# deepblue.net
KiCad netlist of a schematic drawn in EAGLE
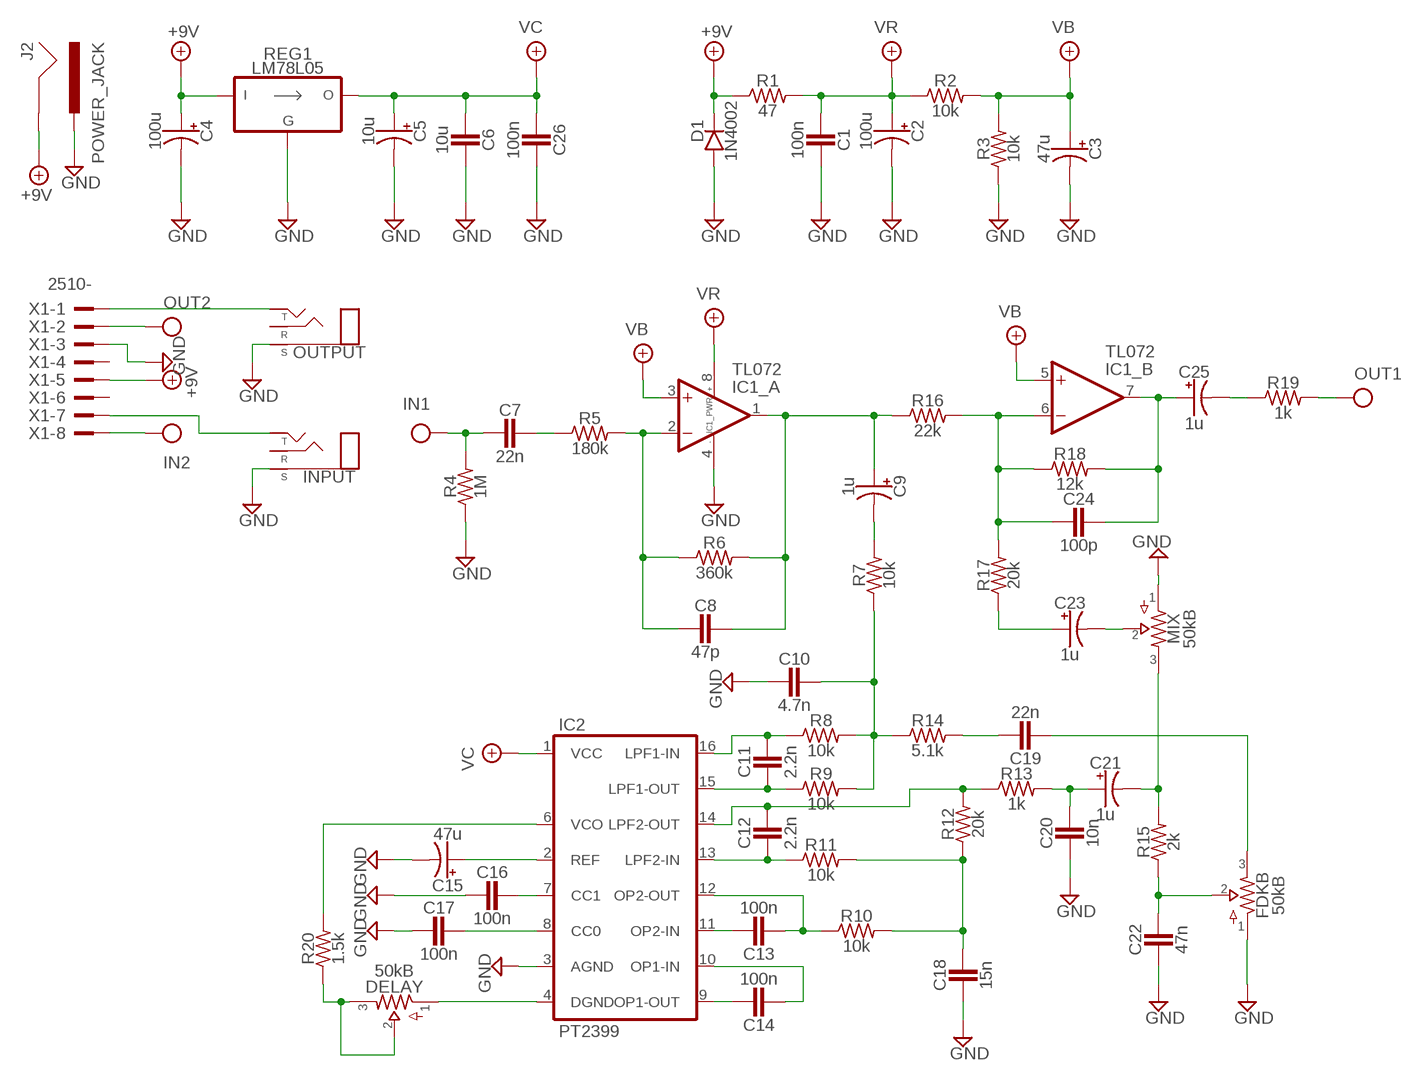
[diagram p0: schematic, sheet 1]

(export (version "E")
  (design (tool "Eeschema 10.0.6"))
  (components
    (comp (ref "C1")
      (value "100n")
      (footprint "eagle-import:050X030_025_2")
      (libsource (lib "eagle-import") (part "CER/FILM2"))
    )
    (comp (ref "C2")
      (value "100u")
      (footprint "eagle-import:050_020")
      (libsource (lib "eagle-import") (part "0500"))
    )
    (comp (ref "C3")
      (value "47u")
      (footprint "eagle-import:050_020")
      (libsource (lib "eagle-import") (part "0500"))
    )
    (comp (ref "C4")
      (value "100u")
      (footprint "eagle-import:050_020")
      (libsource (lib "eagle-import") (part "0500"))
    )
    (comp (ref "C5")
      (value "10u")
      (footprint "eagle-import:050_020")
      (libsource (lib "eagle-import") (part "0500"))
    )
    (comp (ref "C6")
      (value "10u")
      (footprint "eagle-import:050X030_025")
      (libsource (lib "eagle-import") (part "CER/FILM1"))
    )
    (comp (ref "C7")
      (value "22n")
      (footprint "eagle-import:BOX_SMALL")
      (libsource (lib "eagle-import") (part "CER/FILMBOX.1"))
    )
    (comp (ref "C8")
      (value "47p")
      (footprint "eagle-import:050X030_025_2")
      (libsource (lib "eagle-import") (part "CER/FILM2"))
    )
    (comp (ref "C9")
      (value "1u")
      (footprint "eagle-import:040_020")
      (libsource (lib "eagle-import") (part "0400"))
    )
    (comp (ref "C10")
      (value "4.7n")
      (footprint "eagle-import:BOX_SMALL")
      (libsource (lib "eagle-import") (part "CER/FILMBOX.1"))
    )
    (comp (ref "C11")
      (value "2.2n")
      (footprint "eagle-import:BOX_SMALL")
      (libsource (lib "eagle-import") (part "CER/FILMBOX.1"))
    )
    (comp (ref "C12")
      (value "2.2n")
      (footprint "eagle-import:BOX_SMALL")
      (libsource (lib "eagle-import") (part "CER/FILMBOX.1"))
    )
    (comp (ref "C13")
      (value "100n")
      (footprint "eagle-import:BOX_SMALL")
      (libsource (lib "eagle-import") (part "CER/FILMBOX.1"))
    )
    (comp (ref "C14")
      (value "100n")
      (footprint "eagle-import:BOX_SMALL")
      (libsource (lib "eagle-import") (part "CER/FILMBOX.1"))
    )
    (comp (ref "C15")
      (value "47u")
      (footprint "eagle-import:050_020")
      (libsource (lib "eagle-import") (part "0500"))
    )
    (comp (ref "C16")
      (value "100n")
      (footprint "eagle-import:BOX_SMALL")
      (libsource (lib "eagle-import") (part "CER/FILMBOX.1"))
    )
    (comp (ref "C17")
      (value "100n")
      (footprint "eagle-import:BOX_SMALL")
      (libsource (lib "eagle-import") (part "CER/FILMBOX.1"))
    )
    (comp (ref "C18")
      (value "15n")
      (footprint "eagle-import:BOX_SMALL")
      (libsource (lib "eagle-import") (part "CER/FILMBOX.1"))
    )
    (comp (ref "C19")
      (value "22n")
      (footprint "eagle-import:BOX_SMALL")
      (libsource (lib "eagle-import") (part "CER/FILMBOX.1"))
    )
    (comp (ref "C20")
      (value "10n")
      (footprint "eagle-import:BOX_SMALL")
      (libsource (lib "eagle-import") (part "CER/FILMBOX.1"))
    )
    (comp (ref "C21")
      (value "1u")
      (footprint "eagle-import:040_020")
      (libsource (lib "eagle-import") (part "0400"))
    )
    (comp (ref "C22")
      (value "47n")
      (footprint "eagle-import:BOX_SMALL")
      (libsource (lib "eagle-import") (part "CER/FILMBOX.1"))
    )
    (comp (ref "C23")
      (value "1u")
      (footprint "eagle-import:040_020")
      (libsource (lib "eagle-import") (part "0400"))
    )
    (comp (ref "C24")
      (value "100p")
      (footprint "eagle-import:050X030_025_2")
      (libsource (lib "eagle-import") (part "CER/FILM2"))
    )
    (comp (ref "C25")
      (value "1u")
      (footprint "eagle-import:040_020")
      (libsource (lib "eagle-import") (part "0400"))
    )
    (comp (ref "C26")
      (value "100n")
      (footprint "eagle-import:050X030_025_2")
      (libsource (lib "eagle-import") (part "CER/FILM2"))
    )
    (comp (ref "D1")
      (value "1N4002")
      (footprint "eagle-import:DO41-2")
      (libsource (lib "eagle-import") (part "DO41.2"))
    )
    (comp (ref "DELAY")
      (value "50kB")
      (footprint "eagle-import:16MM")
      (libsource (lib "eagle-import") (part "POTS16MM"))
    )
    (comp (ref "FDKB")
      (value "50kB")
      (footprint "eagle-import:16MM")
      (libsource (lib "eagle-import") (part "POTS16MM"))
    )
    (comp (ref "IC1")
      (value "TL072")
      (footprint "eagle-import:DIL0")
      (libsource (lib "eagle-import") (part "DUALTH"))
    )
    (comp (ref "IC2")
      (value "PT2399")
      (footprint "eagle-import:DIL16")
      (libsource (lib "eagle-import") (part "PT2399TH"))
    )
    (comp (ref "INPUT")
      (value "STEREONMJ")
      (footprint "eagle-import:NMJ6HCD2")
      (libsource (lib "eagle-import") (part "STEREONMJ"))
    )
    (comp (ref "J2")
      (value "POWER_JACK")
      (footprint "eagle-import:POWER_JACK_PTH")
      (libsource (lib "eagle-import") (part "POWER_JACK"))
    )
    (comp (ref "MIX")
      (value "50kB")
      (footprint "eagle-import:16MM")
      (libsource (lib "eagle-import") (part "POTS16MM"))
    )
    (comp (ref "OUTPUT")
      (value "STEREONMJ")
      (footprint "eagle-import:NMJ6HCD2")
      (libsource (lib "eagle-import") (part "STEREONMJ"))
    )
    (comp (ref "R1")
      (value "47")
      (footprint "eagle-import:R0207_3")
      (libsource (lib "eagle-import") (part "R_.3B"))
    )
    (comp (ref "R2")
      (value "10k")
      (footprint "eagle-import:R0207_3")
      (libsource (lib "eagle-import") (part "R_.3B"))
    )
    (comp (ref "R3")
      (value "10k")
      (footprint "eagle-import:R0207_3")
      (libsource (lib "eagle-import") (part "R_.3B"))
    )
    (comp (ref "R4")
      (value "1M")
      (footprint "eagle-import:R0207_3")
      (libsource (lib "eagle-import") (part "R_.3B"))
    )
    (comp (ref "R5")
      (value "180k")
      (footprint "eagle-import:R0207_3")
      (libsource (lib "eagle-import") (part "R_.3B"))
    )
    (comp (ref "R6")
      (value "360k")
      (footprint "eagle-import:R0207_3")
      (libsource (lib "eagle-import") (part "R_.3B"))
    )
    (comp (ref "R7")
      (value "10k")
      (footprint "eagle-import:R0207_3")
      (libsource (lib "eagle-import") (part "R_.3B"))
    )
    (comp (ref "R8")
      (value "10k")
      (footprint "eagle-import:R0207_3")
      (libsource (lib "eagle-import") (part "R_.3B"))
    )
    (comp (ref "R9")
      (value "10k")
      (footprint "eagle-import:R0207_3")
      (libsource (lib "eagle-import") (part "R_.3B"))
    )
    (comp (ref "R10")
      (value "10k")
      (footprint "eagle-import:R0207_3")
      (libsource (lib "eagle-import") (part "R_.3B"))
    )
    (comp (ref "R11")
      (value "10k")
      (footprint "eagle-import:R0207_3")
      (libsource (lib "eagle-import") (part "R_.3B"))
    )
    (comp (ref "R12")
      (value "20k")
      (footprint "eagle-import:R0207_3")
      (libsource (lib "eagle-import") (part "R_.3B"))
    )
    (comp (ref "R13")
      (value "1k")
      (footprint "eagle-import:R0207_3")
      (libsource (lib "eagle-import") (part "R_.3B"))
    )
    (comp (ref "R14")
      (value "5.1k")
      (footprint "eagle-import:R0207_3")
      (libsource (lib "eagle-import") (part "R_.3B"))
    )
    (comp (ref "R15")
      (value "2k")
      (footprint "eagle-import:R0207_3")
      (libsource (lib "eagle-import") (part "R_.3B"))
    )
    (comp (ref "R16")
      (value "22k")
      (footprint "eagle-import:R0207_3")
      (libsource (lib "eagle-import") (part "R_.3B"))
    )
    (comp (ref "R17")
      (value "20k")
      (footprint "eagle-import:R0207_3")
      (libsource (lib "eagle-import") (part "R_.3B"))
    )
    (comp (ref "R18")
      (value "12k")
      (footprint "eagle-import:R0207_3")
      (libsource (lib "eagle-import") (part "R_.3B"))
    )
    (comp (ref "R19")
      (value "1k")
      (footprint "eagle-import:R0207_3")
      (libsource (lib "eagle-import") (part "R_.3B"))
    )
    (comp (ref "R20")
      (value "1.5k")
      (footprint "eagle-import:R0207_3")
      (libsource (lib "eagle-import") (part "R_.3B"))
    )
    (comp (ref "REG1")
      (value "LM78L05")
      (footprint "eagle-import:TO92-")
      (libsource (lib "eagle-import") (part "LM78L05"))
    )
    (comp (ref "X1")
      (value "2510-")
      (footprint "eagle-import:PAK100_2500-10")
      (fields (field (name "MF") "3M") (field (name "MPN") "2510-6002UB"))
      (libsource (lib "eagle-import") (part "2510-"))
    )
  )
  (nets
    (net (code "1") (name "+9V") (class "Default")
      (node (ref "C4") (pin "+") (pinfunction "+_+") (pintype "passive"))
      (node (ref "D1") (pin "C") (pinfunction "C_C") (pintype "passive"))
      (node (ref "J2") (pin "GND") (pinfunction "GND_GND") (pintype "bidirectional"))
      (node (ref "R1") (pin "1") (pinfunction "1_1") (pintype "passive"))
      (node (ref "REG1") (pin "1") (pinfunction "VI_1") (pintype "input"))
      (node (ref "X1") (pin "5") (pinfunction "KL_5") (pintype "passive"))
    )
    (net (code "2") (name "GND") (class "Default")
      (node (ref "C1") (pin "1") (pinfunction "1_1") (pintype "passive"))
      (node (ref "C10") (pin "2") (pinfunction "2_2") (pintype "passive"))
      (node (ref "C15") (pin "-") (pinfunction "-_-") (pintype "passive"))
      (node (ref "C16") (pin "2") (pinfunction "2_2") (pintype "passive"))
      (node (ref "C17") (pin "2") (pinfunction "2_2") (pintype "passive"))
      (node (ref "C18") (pin "2") (pinfunction "2_2") (pintype "passive"))
      (node (ref "C2") (pin "-") (pinfunction "-_-") (pintype "passive"))
      (node (ref "C20") (pin "2") (pinfunction "2_2") (pintype "passive"))
      (node (ref "C22") (pin "2") (pinfunction "2_2") (pintype "passive"))
      (node (ref "C26") (pin "1") (pinfunction "1_1") (pintype "passive"))
      (node (ref "C3") (pin "-") (pinfunction "-_-") (pintype "passive"))
      (node (ref "C4") (pin "-") (pinfunction "-_-") (pintype "passive"))
      (node (ref "C5") (pin "-") (pinfunction "-_-") (pintype "passive"))
      (node (ref "C6") (pin "1") (pinfunction "1_1") (pintype "passive"))
      (node (ref "D1") (pin "A") (pinfunction "A_A") (pintype "passive"))
      (node (ref "FDKB") (pin "1") (pinfunction "1_1") (pintype "passive"))
      (node (ref "IC1") (pin "4") (pinfunction "V-_4") (pintype "power_in"))
      (node (ref "IC2") (pin "3") (pinfunction "AGND_3") (pintype "power_in"))
      (node (ref "INPUT") (pin "S") (pinfunction "S_S") (pintype "passive"))
      (node (ref "J2") (pin "PWR") (pinfunction "PWR_PWR") (pintype "bidirectional"))
      (node (ref "MIX") (pin "1") (pinfunction "1_1") (pintype "passive"))
      (node (ref "OUTPUT") (pin "S") (pinfunction "S_S") (pintype "passive"))
      (node (ref "R3") (pin "1") (pinfunction "1_1") (pintype "passive"))
      (node (ref "R4") (pin "1") (pinfunction "1_1") (pintype "passive"))
      (node (ref "REG1") (pin "2") (pinfunction "GND_2") (pintype "passive"))
      (node (ref "X1") (pin "3") (pinfunction "KL_3") (pintype "passive"))
    )
    (net (code "3") (name "IN") (class "Default")
      (node (ref "C7") (pin "2") (pinfunction "2_2") (pintype "passive"))
      (node (ref "R4") (pin "2") (pinfunction "2_2") (pintype "passive"))
      (node (ref "X1") (pin "8") (pinfunction "KL_8") (pintype "passive"))
    )
    (net (code "4") (name "Net-(C7-Pad1)") (class "Default")
      (node (ref "C7") (pin "1") (pinfunction "1_1") (pintype "passive"))
      (node (ref "R5") (pin "1") (pinfunction "1_1") (pintype "passive"))
    )
    (net (code "5") (name "Net-(C9-Pad-)") (class "Default")
      (node (ref "C9") (pin "-") (pinfunction "-_-") (pintype "passive"))
      (node (ref "R7") (pin "2") (pinfunction "2_2") (pintype "passive"))
    )
    (net (code "6") (name "Net-(C10-Pad1)") (class "Default")
      (node (ref "C10") (pin "1") (pinfunction "1_1") (pintype "passive"))
      (node (ref "R14") (pin "1") (pinfunction "1_1") (pintype "passive"))
      (node (ref "R7") (pin "1") (pinfunction "1_1") (pintype "passive"))
      (node (ref "R8") (pin "2") (pinfunction "2_2") (pintype "passive"))
      (node (ref "R9") (pin "2") (pinfunction "2_2") (pintype "passive"))
    )
    (net (code "7") (name "Net-(C18-Pad1)") (class "Default")
      (node (ref "C18") (pin "1") (pinfunction "1_1") (pintype "passive"))
      (node (ref "R10") (pin "2") (pinfunction "2_2") (pintype "passive"))
      (node (ref "R11") (pin "2") (pinfunction "2_2") (pintype "passive"))
      (node (ref "R12") (pin "1") (pinfunction "1_1") (pintype "passive"))
    )
    (net (code "8") (name "Net-(C19-Pad1)") (class "Default")
      (node (ref "C19") (pin "1") (pinfunction "1_1") (pintype "passive"))
      (node (ref "R14") (pin "2") (pinfunction "2_2") (pintype "passive"))
    )
    (net (code "9") (name "Net-(C19-Pad2)") (class "Default")
      (node (ref "C19") (pin "2") (pinfunction "2_2") (pintype "passive"))
      (node (ref "FDKB") (pin "3") (pinfunction "3_3") (pintype "passive"))
    )
    (net (code "10") (name "Net-(C20-Pad1)") (class "Default")
      (node (ref "C20") (pin "1") (pinfunction "1_1") (pintype "passive"))
      (node (ref "C21") (pin "+") (pinfunction "+_+") (pintype "passive"))
      (node (ref "R13") (pin "2") (pinfunction "2_2") (pintype "passive"))
    )
    (net (code "11") (name "Net-(C21-Pad-)") (class "Default")
      (node (ref "C21") (pin "-") (pinfunction "-_-") (pintype "passive"))
      (node (ref "MIX") (pin "3") (pinfunction "3_3") (pintype "passive"))
      (node (ref "R15") (pin "2") (pinfunction "2_2") (pintype "passive"))
    )
    (net (code "12") (name "Net-(C22-Pad1)") (class "Default")
      (node (ref "C22") (pin "1") (pinfunction "1_1") (pintype "passive"))
      (node (ref "FDKB") (pin "2") (pinfunction "2_2") (pintype "passive"))
      (node (ref "R15") (pin "1") (pinfunction "1_1") (pintype "passive"))
    )
    (net (code "13") (name "Net-(C23-Pad+)") (class "Default")
      (node (ref "C23") (pin "+") (pinfunction "+_+") (pintype "passive"))
      (node (ref "R17") (pin "1") (pinfunction "1_1") (pintype "passive"))
    )
    (net (code "14") (name "Net-(C23-Pad-)") (class "Default")
      (node (ref "C23") (pin "-") (pinfunction "-_-") (pintype "passive"))
      (node (ref "MIX") (pin "2") (pinfunction "2_2") (pintype "passive"))
    )
    (net (code "15") (name "Net-(C25-Pad-)") (class "Default")
      (node (ref "C25") (pin "-") (pinfunction "-_-") (pintype "passive"))
      (node (ref "R19") (pin "1") (pinfunction "1_1") (pintype "passive"))
    )
    (net (code "16") (name "Net-(DELAY-Pad2)") (class "Default")
      (node (ref "DELAY") (pin "2") (pinfunction "2_2") (pintype "passive"))
      (node (ref "DELAY") (pin "3") (pinfunction "3_3") (pintype "passive"))
      (node (ref "R20") (pin "1") (pinfunction "1_1") (pintype "passive"))
    )
    (net (code "17") (name "Net-(IC1A--IN)") (class "Default")
      (node (ref "C8") (pin "2") (pinfunction "2_2") (pintype "passive"))
      (node (ref "IC1") (pin "2") (pinfunction "-IN_2") (pintype "input"))
      (node (ref "R5") (pin "2") (pinfunction "2_2") (pintype "passive"))
      (node (ref "R6") (pin "1") (pinfunction "1_1") (pintype "passive"))
    )
    (net (code "18") (name "Net-(IC1A-OUT)") (class "Default")
      (node (ref "C8") (pin "1") (pinfunction "1_1") (pintype "passive"))
      (node (ref "C9") (pin "+") (pinfunction "+_+") (pintype "passive"))
      (node (ref "IC1") (pin "1") (pinfunction "OUT_1") (pintype "output"))
      (node (ref "R16") (pin "1") (pinfunction "1_1") (pintype "passive"))
      (node (ref "R6") (pin "2") (pinfunction "2_2") (pintype "passive"))
    )
    (net (code "19") (name "Net-(IC1B--IN)") (class "Default")
      (node (ref "C24") (pin "2") (pinfunction "2_2") (pintype "passive"))
      (node (ref "IC1") (pin "6") (pinfunction "-IN_6") (pintype "input"))
      (node (ref "R16") (pin "2") (pinfunction "2_2") (pintype "passive"))
      (node (ref "R17") (pin "2") (pinfunction "2_2") (pintype "passive"))
      (node (ref "R18") (pin "1") (pinfunction "1_1") (pintype "passive"))
    )
    (net (code "20") (name "Net-(IC1B-OUT)") (class "Default")
      (node (ref "C24") (pin "1") (pinfunction "1_1") (pintype "passive"))
      (node (ref "C25") (pin "+") (pinfunction "+_+") (pintype "passive"))
      (node (ref "IC1") (pin "7") (pinfunction "OUT_7") (pintype "output"))
      (node (ref "R18") (pin "2") (pinfunction "2_2") (pintype "passive"))
    )
    (net (code "21") (name "Net-(IC2-CC0)") (class "Default")
      (node (ref "C17") (pin "1") (pinfunction "1_1") (pintype "passive"))
      (node (ref "IC2") (pin "8") (pinfunction "CC0_8") (pintype "input"))
    )
    (net (code "22") (name "Net-(IC2-CC1)") (class "Default")
      (node (ref "C16") (pin "1") (pinfunction "1_1") (pintype "passive"))
      (node (ref "IC2") (pin "7") (pinfunction "CC1_7") (pintype "input"))
    )
    (net (code "23") (name "Net-(IC2-DGND)") (class "Default")
      (node (ref "DELAY") (pin "1") (pinfunction "1_1") (pintype "passive"))
      (node (ref "IC2") (pin "4") (pinfunction "DGND_4") (pintype "power_in"))
    )
    (net (code "24") (name "Net-(IC2-LPF1-IN)") (class "Default")
      (node (ref "C11") (pin "1") (pinfunction "1_1") (pintype "passive"))
      (node (ref "IC2") (pin "16") (pinfunction "LPF1-IN_16") (pintype "input"))
      (node (ref "R8") (pin "1") (pinfunction "1_1") (pintype "passive"))
    )
    (net (code "25") (name "Net-(IC2-LPF1-OUT)") (class "Default")
      (node (ref "C11") (pin "2") (pinfunction "2_2") (pintype "passive"))
      (node (ref "IC2") (pin "15") (pinfunction "LPF1-OUT_15") (pintype "output"))
      (node (ref "R9") (pin "1") (pinfunction "1_1") (pintype "passive"))
    )
    (net (code "26") (name "Net-(IC2-LPF2-IN)") (class "Default")
      (node (ref "C12") (pin "2") (pinfunction "2_2") (pintype "passive"))
      (node (ref "IC2") (pin "13") (pinfunction "LPF2-IN_13") (pintype "input"))
      (node (ref "R11") (pin "1") (pinfunction "1_1") (pintype "passive"))
    )
    (net (code "27") (name "Net-(IC2-LPF2-OUT)") (class "Default")
      (node (ref "C12") (pin "1") (pinfunction "1_1") (pintype "passive"))
      (node (ref "IC2") (pin "14") (pinfunction "LPF2-OUT_14") (pintype "output"))
      (node (ref "R12") (pin "2") (pinfunction "2_2") (pintype "passive"))
      (node (ref "R13") (pin "1") (pinfunction "1_1") (pintype "passive"))
    )
    (net (code "28") (name "Net-(IC2-OP1-IN)") (class "Default")
      (node (ref "C14") (pin "2") (pinfunction "2_2") (pintype "passive"))
      (node (ref "IC2") (pin "10") (pinfunction "OP1-IN_10") (pintype "input"))
    )
    (net (code "29") (name "Net-(IC2-OP1-OUT)") (class "Default")
      (node (ref "C14") (pin "1") (pinfunction "1_1") (pintype "passive"))
      (node (ref "IC2") (pin "9") (pinfunction "OP1-OUT_9") (pintype "output"))
    )
    (net (code "30") (name "Net-(IC2-OP2-IN)") (class "Default")
      (node (ref "C13") (pin "1") (pinfunction "1_1") (pintype "passive"))
      (node (ref "IC2") (pin "11") (pinfunction "OP2-IN_11") (pintype "input"))
    )
    (net (code "31") (name "Net-(IC2-OP2-OUT)") (class "Default")
      (node (ref "C13") (pin "2") (pinfunction "2_2") (pintype "passive"))
      (node (ref "IC2") (pin "12") (pinfunction "OP2-OUT_12") (pintype "output"))
      (node (ref "R10") (pin "1") (pinfunction "1_1") (pintype "passive"))
    )
    (net (code "32") (name "Net-(IC2-REF)") (class "Default")
      (node (ref "C15") (pin "+") (pinfunction "+_+") (pintype "passive"))
      (node (ref "IC2") (pin "2") (pinfunction "REF_2") (pintype "input"))
    )
    (net (code "33") (name "Net-(IC2-VCO)") (class "Default")
      (node (ref "IC2") (pin "6") (pinfunction "VCO_6") (pintype "input"))
      (node (ref "R20") (pin "2") (pinfunction "2_2") (pintype "passive"))
    )
    (net (code "34") (name "Net-(X1A-KL)") (class "Default")
      (node (ref "OUTPUT") (pin "T") (pinfunction "T_T") (pintype "passive"))
      (node (ref "X1") (pin "1") (pinfunction "KL_1") (pintype "passive"))
    )
    (net (code "35") (name "Net-(X1G-KL)") (class "Default")
      (node (ref "INPUT") (pin "T") (pinfunction "T_T") (pintype "passive"))
      (node (ref "X1") (pin "7") (pinfunction "KL_7") (pintype "passive"))
    )
    (net (code "36") (name "OUT") (class "Default")
      (node (ref "R19") (pin "2") (pinfunction "2_2") (pintype "passive"))
      (node (ref "X1") (pin "2") (pinfunction "KL_2") (pintype "passive"))
    )
    (net (code "37") (name "VB") (class "Default")
      (node (ref "C3") (pin "+") (pinfunction "+_+") (pintype "passive"))
      (node (ref "IC1") (pin "3") (pinfunction "+IN_3") (pintype "input"))
      (node (ref "IC1") (pin "5") (pinfunction "+IN_5") (pintype "input"))
      (node (ref "R2") (pin "2") (pinfunction "2_2") (pintype "passive"))
      (node (ref "R3") (pin "2") (pinfunction "2_2") (pintype "passive"))
    )
    (net (code "38") (name "VC") (class "Default")
      (node (ref "C26") (pin "2") (pinfunction "2_2") (pintype "passive"))
      (node (ref "C5") (pin "+") (pinfunction "+_+") (pintype "passive"))
      (node (ref "C6") (pin "2") (pinfunction "2_2") (pintype "passive"))
      (node (ref "IC2") (pin "1") (pinfunction "VCC_1") (pintype "power_in"))
      (node (ref "REG1") (pin "3") (pinfunction "VO_3") (pintype "passive"))
    )
    (net (code "39") (name "VR") (class "Default")
      (node (ref "C1") (pin "2") (pinfunction "2_2") (pintype "passive"))
      (node (ref "C2") (pin "+") (pinfunction "+_+") (pintype "passive"))
      (node (ref "IC1") (pin "8") (pinfunction "V+_8") (pintype "power_in"))
      (node (ref "R1") (pin "2") (pinfunction "2_2") (pintype "passive"))
      (node (ref "R2") (pin "1") (pinfunction "1_1") (pintype "passive"))
    )
    (net (code "40") (name "unconnected-(INPUT-PadR)") (class "Default")
      (node (ref "INPUT") (pin "R") (pinfunction "R_R") (pintype "passive"))
    )
    (net (code "41") (name "unconnected-(OUTPUT-PadR)") (class "Default")
      (node (ref "OUTPUT") (pin "R") (pinfunction "R_R") (pintype "passive"))
    )
    (net (code "42") (name "unconnected-(X1D-KL-Pad4)") (class "Default")
      (node (ref "X1") (pin "4") (pinfunction "KL_4") (pintype "passive"))
    )
    (net (code "43") (name "unconnected-(X1F-KL-Pad6)") (class "Default")
      (node (ref "X1") (pin "6") (pinfunction "KL_6") (pintype "passive"))
    )
  )
)
